# SchmaticX.net
KiCad netlist of a schematic drawn in Altium Designer
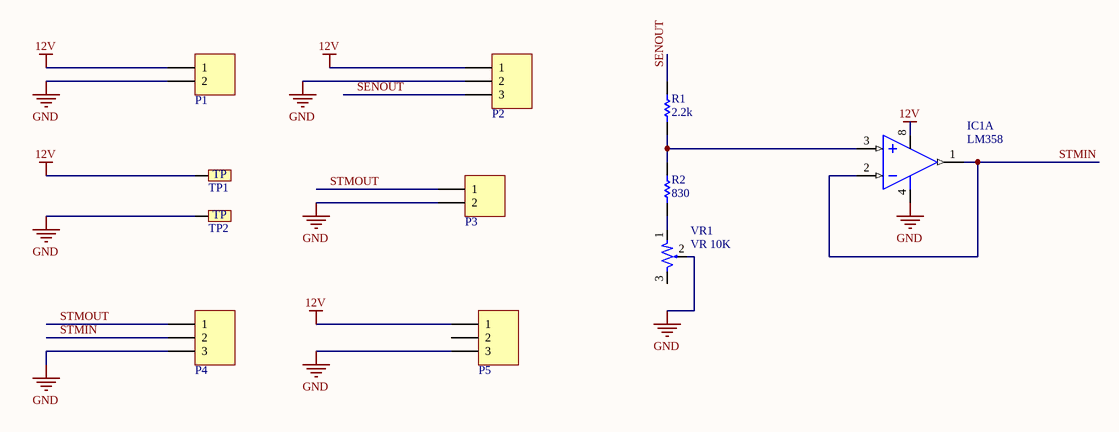
[diagram p0: SchmaticX.SchDoc]

(export (version "E")
  (design (tool "Eeschema 10.0.6"))
  (components
    (comp (ref "IC1")
      (value "LM358")
      (footprint "DIP8")
      (description "Low-Power Dual Operational Amplifier")
      (libsource (lib "LIBRARY") (part "LM358"))
    )
    (comp (ref "P1")
      (value "Domino 2")
      (footprint "DOMINO 2- 5mm")
      (description "Domino, 2-Pin")
      (fields (field (name "PUBLISHER") "Altium Limited"))
      (libsource (lib "PIF_Library") (part "Domino 2"))
    )
    (comp (ref "P2")
      (value "Header 3")
      (footprint "JP3")
      (description "Header, 3-Pin")
      (fields (field (name "PUBLISHER") "Altium Limited"))
      (libsource (lib "PIF_Library") (part "Header 3"))
    )
    (comp (ref "P3")
      (value "Domino 2")
      (footprint "DOMINO 2- 5mm")
      (description "Domino, 2-Pin")
      (fields (field (name "PUBLISHER") "Altium Limited"))
      (libsource (lib "PIF_Library") (part "Domino 2"))
    )
    (comp (ref "P4")
      (value "Header 3")
      (footprint "JP3")
      (description "Header, 3-Pin")
      (fields (field (name "PUBLISHER") "Altium Limited"))
      (libsource (lib "PIF_Library") (part "Header 3"))
    )
    (comp (ref "P5")
      (value "Domino 3")
      (footprint "DOMINO 3-5mm")
      (description "Domino 3-Pin")
      (fields (field (name "PUBLISHER") "Altium Limited"))
      (libsource (lib "PIF_Library") (part "Domino 3"))
    )
    (comp (ref "R1")
      (value "2.2k")
      (footprint "RES-SM-0805")
      (description "Resistor")
      (fields (field (name "Comment") "RESISTOR SMD"))
      (libsource (lib "PIF_Library") (part "RESISTOR SMD"))
    )
    (comp (ref "R2")
      (value "830")
      (footprint "RES-SM-0805")
      (description "Resistor")
      (fields (field (name "Comment") "RESISTOR SMD"))
      (libsource (lib "PIF_Library") (part "RESISTOR SMD"))
    )
    (comp (ref "TP1")
      (value "Test Point")
      (footprint "TP")
      (libsource (lib "PIF_Library") (part "Test Point"))
    )
    (comp (ref "TP2")
      (value "Test Point")
      (footprint "TP")
      (libsource (lib "PIF_Library") (part "Test Point"))
    )
    (comp (ref "VR1")
      (value "VR 10K")
      (footprint "Varistor 1")
      (description "Var Resistor")
      (fields (field (name "Comment") "10K"))
      (libsource (lib "PIF_Library") (part "Var Resistor"))
    )
  )
  (nets
    (net (code "1") (name "/SENOUT") (class "Default")
      (node (ref "P2") (pin "3") (pinfunction "3_3") (pintype "passive"))
      (node (ref "R1") (pin "2") (pinfunction "2_2") (pintype "passive"))
    )
    (net (code "2") (name "/STMIN") (class "Default")
      (node (ref "IC1") (pin "1") (pinfunction "OUT_1") (pintype "output"))
      (node (ref "IC1") (pin "2") (pinfunction "IN-_2") (pintype "input"))
      (node (ref "P4") (pin "2") (pinfunction "2_2") (pintype "passive"))
    )
    (net (code "3") (name "/STMOUT") (class "Default")
      (node (ref "P3") (pin "1") (pinfunction "1_1") (pintype "passive"))
      (node (ref "P4") (pin "1") (pinfunction "1_1") (pintype "passive"))
    )
    (net (code "4") (name "12V") (class "Default")
      (node (ref "IC1") (pin "8") (pinfunction "+V_8") (pintype "passive"))
      (node (ref "P1") (pin "1") (pinfunction "1_1") (pintype "passive"))
      (node (ref "P2") (pin "1") (pinfunction "1_1") (pintype "passive"))
      (node (ref "P5") (pin "1") (pinfunction "1_1") (pintype "passive"))
      (node (ref "TP1") (pin "TP1") (pinfunction "0_TP1") (pintype "passive"))
    )
    (net (code "5") (name "GND") (class "Default")
      (node (ref "IC1") (pin "4") (pinfunction "-V_4") (pintype "passive"))
      (node (ref "P1") (pin "2") (pinfunction "2_2") (pintype "passive"))
      (node (ref "P2") (pin "2") (pinfunction "2_2") (pintype "passive"))
      (node (ref "P3") (pin "2") (pinfunction "2_2") (pintype "passive"))
      (node (ref "P4") (pin "3") (pinfunction "3_3") (pintype "passive"))
      (node (ref "P5") (pin "3") (pinfunction "3_3") (pintype "passive"))
      (node (ref "TP2") (pin "TP1") (pinfunction "0_TP1") (pintype "passive"))
      (node (ref "VR1") (pin "2") (pinfunction "2_2") (pintype "passive"))
    )
    (net (code "6") (name "Net-(IC1A-IN+)") (class "Default")
      (node (ref "IC1") (pin "3") (pinfunction "IN+_3") (pintype "input"))
      (node (ref "R1") (pin "1") (pinfunction "1_1") (pintype "passive"))
      (node (ref "R2") (pin "2") (pinfunction "2_2") (pintype "passive"))
    )
    (net (code "7") (name "Net-(R2-Pad1)") (class "Default")
      (node (ref "R2") (pin "1") (pinfunction "1_1") (pintype "passive"))
      (node (ref "VR1") (pin "1") (pinfunction "1_1") (pintype "passive"))
    )
    (net (code "8") (name "unconnected-(P5-Pad2)") (class "Default")
      (node (ref "P5") (pin "2") (pinfunction "2_2") (pintype "passive"))
    )
    (net (code "9") (name "unconnected-(VR1-Pad3)") (class "Default")
      (node (ref "VR1") (pin "3") (pinfunction "3_3") (pintype "passive"))
    )
  )
)
